# tiny_metal_detector.net
KiCad netlist of a schematic drawn in EAGLE
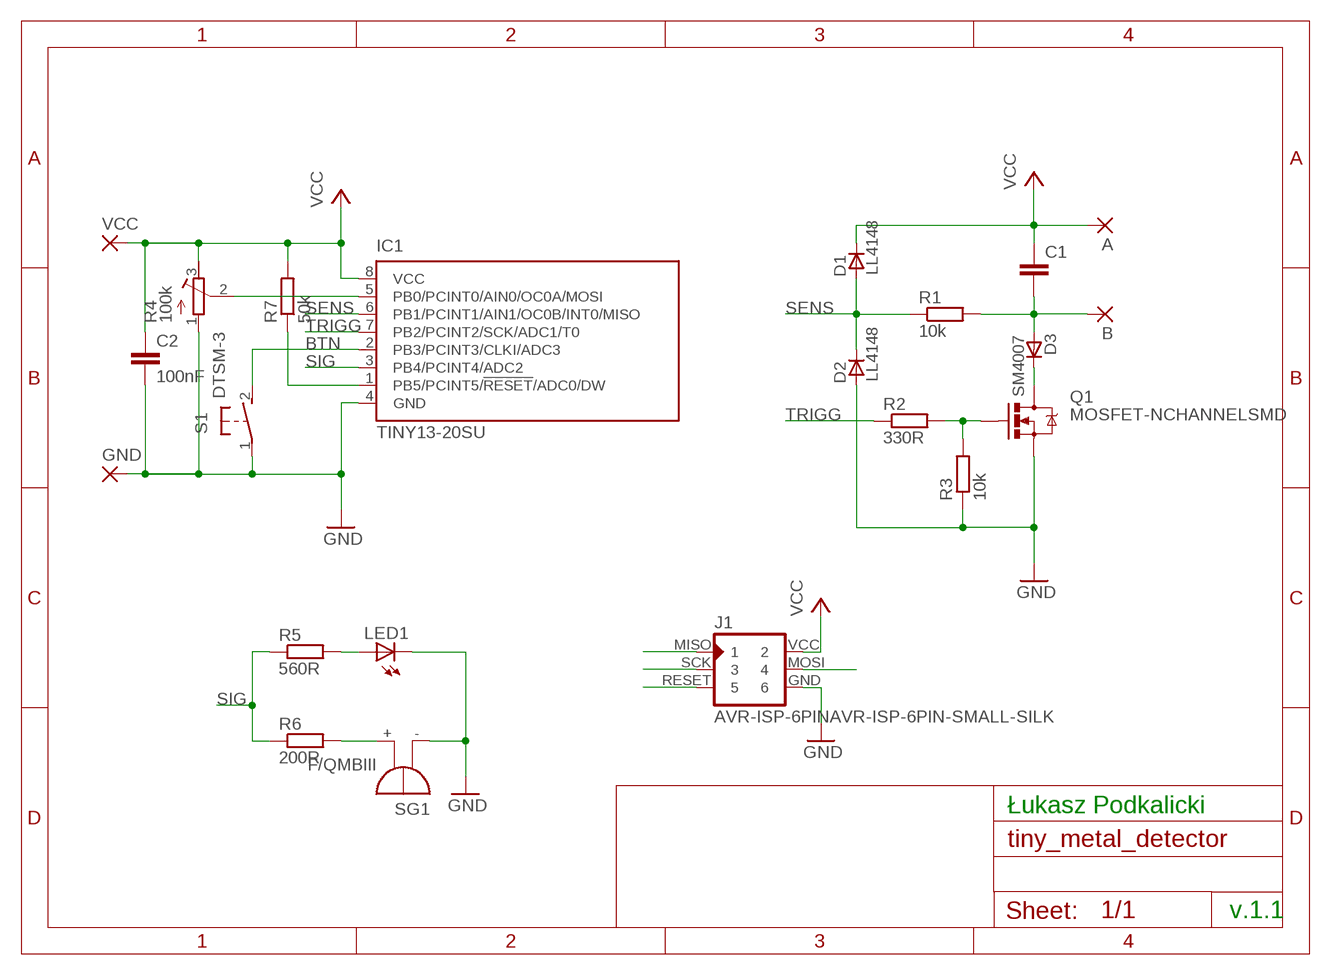
[diagram p0: schematic, sheet 1]

(export (version "E")
  (design (tool "Eeschema 10.0.6"))
  (components
    (comp (ref "A")
      (value "3,17/1,1")
      (footprint "eagle-import:3,17_1,1")
      (libsource (lib "eagle-import") (part "3,17/1,1"))
    )
    (comp (ref "B")
      (value "3,17/1,1")
      (footprint "eagle-import:3,17_1,1")
      (libsource (lib "eagle-import") (part "3,17/1,1"))
    )
    (comp (ref "C1")
      (value "C-EUC1206K")
      (footprint "eagle-import:C1206K")
      (libsource (lib "eagle-import") (part "C-EUC1206K"))
    )
    (comp (ref "C2")
      (value "100nF")
      (footprint "eagle-import:C1206K")
      (libsource (lib "eagle-import") (part "C-EUC1206K"))
    )
    (comp (ref "D1")
      (value "LL4148")
      (footprint "eagle-import:SOD80_DO213AA_MINIMELF")
      (libsource (lib "eagle-import") (part "LL4148"))
    )
    (comp (ref "D2")
      (value "LL4148")
      (footprint "eagle-import:SOD80_DO213AA_MINIMELF")
      (libsource (lib "eagle-import") (part "LL4148"))
    )
    (comp (ref "D3")
      (value "SM4007")
      (footprint "eagle-import:MELF-MLL41_DO213AB")
      (libsource (lib "eagle-import") (part "SM4007"))
    )
    (comp (ref "GND")
      (value "3,17/1,1")
      (footprint "eagle-import:3,17_1,1")
      (libsource (lib "eagle-import") (part "3,17/1,1"))
    )
    (comp (ref "IC1")
      (value "TINY13-20SU")
      (footprint "eagle-import:8S2")
      (fields (field (name "MPN") "ATTINY13-20SU"))
      (libsource (lib "eagle-import") (part "TINY13SU-20"))
    )
    (comp (ref "J1")
      (value "AVR-ISP-6PINAVR-ISP-6PIN-SMALL-SILK")
      (footprint "eagle-import:AVR-ISP-6PIN-SMAILL-SILK")
      (libsource (lib "eagle-import") (part "AVR-ISP-6PINAVR-ISP-6PIN-SMALL-SILK"))
    )
    (comp (ref "LED1")
      (value "LEDCHIPLED_1206")
      (footprint "eagle-import:CHIPLED_1206")
      (libsource (lib "eagle-import") (part "LEDCHIPLED_1206"))
    )
    (comp (ref "Q1")
      (value "MOSFET-NCHANNELSMD")
      (footprint "eagle-import:SOT23-3")
      (libsource (lib "eagle-import") (part "MOSFET-NCHANNELSMD"))
    )
    (comp (ref "R1")
      (value "10k")
      (footprint "eagle-import:R1206")
      (libsource (lib "eagle-import") (part "R-EU_R1206"))
    )
    (comp (ref "R2")
      (value "330R")
      (footprint "eagle-import:R1206")
      (libsource (lib "eagle-import") (part "R-EU_R1206"))
    )
    (comp (ref "R3")
      (value "10k")
      (footprint "eagle-import:R1206")
      (libsource (lib "eagle-import") (part "R-EU_R1206"))
    )
    (comp (ref "R4")
      (value "100k")
      (footprint "eagle-import:RTRIM3296W")
      (libsource (lib "eagle-import") (part "R-TRIMM3296W"))
    )
    (comp (ref "R5")
      (value "560R")
      (footprint "eagle-import:R1206")
      (libsource (lib "eagle-import") (part "R-EU_R1206"))
    )
    (comp (ref "R6")
      (value "200R")
      (footprint "eagle-import:R1206")
      (libsource (lib "eagle-import") (part "R-EU_R1206"))
    )
    (comp (ref "R7")
      (value "50k")
      (footprint "eagle-import:R1206")
      (libsource (lib "eagle-import") (part "R-EU_R1206"))
    )
    (comp (ref "S1")
      (value "DTSM-3")
      (footprint "eagle-import:DTSM-3")
      (libsource (lib "eagle-import") (part "DTSM-3"))
    )
    (comp (ref "SG1")
      (value "F/QMBIII")
      (footprint "eagle-import:F_QMBIII")
      (libsource (lib "eagle-import") (part "F/QMBIII"))
    )
    (comp (ref "VCC")
      (value "3,17/1,1")
      (footprint "eagle-import:3,17_1,1")
      (libsource (lib "eagle-import") (part "3,17/1,1"))
    )
  )
  (nets
    (net (code "1") (name "/BTN") (class "Default")
      (node (ref "IC1") (pin "2") (pinfunction "PB3/PCINT3/CLKI/ADC3_2") (pintype "bidirectional"))
      (node (ref "S1") (pin "2") (pinfunction "2_2") (pintype "passive"))
    )
    (net (code "2") (name "/MOSI") (class "Default")
      (node (ref "IC1") (pin "5") (pinfunction "PB0/PCINT0/AIN0/OC0A/MOSI_5") (pintype "bidirectional"))
      (node (ref "J1") (pin "MOSI") (pinfunction "4_MOSI") (pintype "passive"))
      (node (ref "R4") (pin "2") (pinfunction "S_2") (pintype "passive"))
    )
    (net (code "3") (name "/RESET") (class "Default")
      (node (ref "IC1") (pin "1") (pinfunction "PB5/PCINT5/~{RESET}/ADC0/DW_1") (pintype "bidirectional"))
      (node (ref "J1") (pin "RESET") (pinfunction "5_RESET") (pintype "passive"))
      (node (ref "R7") (pin "1") (pinfunction "1_1") (pintype "passive"))
    )
    (net (code "4") (name "/SENS") (class "Default")
      (node (ref "D1") (pin "A") (pinfunction "A_A") (pintype "passive"))
      (node (ref "D2") (pin "C") (pinfunction "C_C") (pintype "passive"))
      (node (ref "IC1") (pin "6") (pinfunction "PB1/PCINT1/AIN1/OC0B/INT0/MISO_6") (pintype "bidirectional"))
      (node (ref "J1") (pin "MISO") (pinfunction "1_MISO") (pintype "passive"))
      (node (ref "R1") (pin "1") (pinfunction "1_1") (pintype "passive"))
    )
    (net (code "5") (name "/SIG") (class "Default")
      (node (ref "IC1") (pin "3") (pinfunction "PB4/PCINT4/ADC2_3") (pintype "bidirectional"))
      (node (ref "R5") (pin "1") (pinfunction "1_1") (pintype "passive"))
      (node (ref "R6") (pin "1") (pinfunction "1_1") (pintype "passive"))
    )
    (net (code "6") (name "/TRIGG") (class "Default")
      (node (ref "IC1") (pin "7") (pinfunction "PB2/PCINT2/SCK/ADC1/T0_7") (pintype "bidirectional"))
      (node (ref "J1") (pin "SCK") (pinfunction "3_SCK") (pintype "passive"))
      (node (ref "R2") (pin "1") (pinfunction "1_1") (pintype "passive"))
    )
    (net (code "7") (name "GND") (class "Default")
      (node (ref "C2") (pin "2") (pinfunction "2_2") (pintype "passive"))
      (node (ref "D2") (pin "A") (pinfunction "A_A") (pintype "passive"))
      (node (ref "GND") (pin "1") (pinfunction "P_1") (pintype "passive"))
      (node (ref "IC1") (pin "4") (pinfunction "GND_4") (pintype "power_in"))
      (node (ref "J1") (pin "GND") (pinfunction "6_GND") (pintype "passive"))
      (node (ref "LED1") (pin "C") (pinfunction "C_C") (pintype "passive"))
      (node (ref "Q1") (pin "2") (pinfunction "S_2") (pintype "passive"))
      (node (ref "R3") (pin "1") (pinfunction "1_1") (pintype "passive"))
      (node (ref "R4") (pin "1") (pinfunction "A_1") (pintype "passive"))
      (node (ref "S1") (pin "1") (pinfunction "1_1") (pintype "passive"))
      (node (ref "SG1") (pin "-") (pinfunction "+_-") (pintype "passive"))
    )
    (net (code "8") (name "Net-(B-P)") (class "Default")
      (node (ref "B") (pin "1") (pinfunction "P_1") (pintype "passive"))
      (node (ref "C1") (pin "2") (pinfunction "2_2") (pintype "passive"))
      (node (ref "D3") (pin "A") (pinfunction "A_A") (pintype "passive"))
      (node (ref "R1") (pin "2") (pinfunction "2_2") (pintype "passive"))
    )
    (net (code "9") (name "Net-(LED1-PadA)") (class "Default")
      (node (ref "LED1") (pin "A") (pinfunction "A_A") (pintype "passive"))
      (node (ref "R5") (pin "2") (pinfunction "2_2") (pintype "passive"))
    )
    (net (code "10") (name "Net-(Q1-D)") (class "Default")
      (node (ref "D3") (pin "C") (pinfunction "C_C") (pintype "passive"))
      (node (ref "Q1") (pin "3") (pinfunction "D_3") (pintype "passive"))
    )
    (net (code "11") (name "Net-(Q1-G)") (class "Default")
      (node (ref "Q1") (pin "1") (pinfunction "G_1") (pintype "passive"))
      (node (ref "R2") (pin "2") (pinfunction "2_2") (pintype "passive"))
      (node (ref "R3") (pin "2") (pinfunction "2_2") (pintype "passive"))
    )
    (net (code "12") (name "Net-(SG1--)") (class "Default")
      (node (ref "R6") (pin "2") (pinfunction "2_2") (pintype "passive"))
      (node (ref "SG1") (pin "+") (pinfunction "-_+") (pintype "passive"))
    )
    (net (code "13") (name "VCC") (class "Default")
      (node (ref "A") (pin "1") (pinfunction "P_1") (pintype "passive"))
      (node (ref "C1") (pin "1") (pinfunction "1_1") (pintype "passive"))
      (node (ref "C2") (pin "1") (pinfunction "1_1") (pintype "passive"))
      (node (ref "D1") (pin "C") (pinfunction "C_C") (pintype "passive"))
      (node (ref "IC1") (pin "8") (pinfunction "VCC_8") (pintype "power_in"))
      (node (ref "J1") (pin "VCC") (pinfunction "2_VCC") (pintype "passive"))
      (node (ref "R4") (pin "3") (pinfunction "E_3") (pintype "passive"))
      (node (ref "R7") (pin "2") (pinfunction "2_2") (pintype "passive"))
      (node (ref "VCC") (pin "1") (pinfunction "P_1") (pintype "passive"))
    )
  )
)
